# 10_ethernet100.net
KiCad netlist of a schematic drawn in Altium Designer
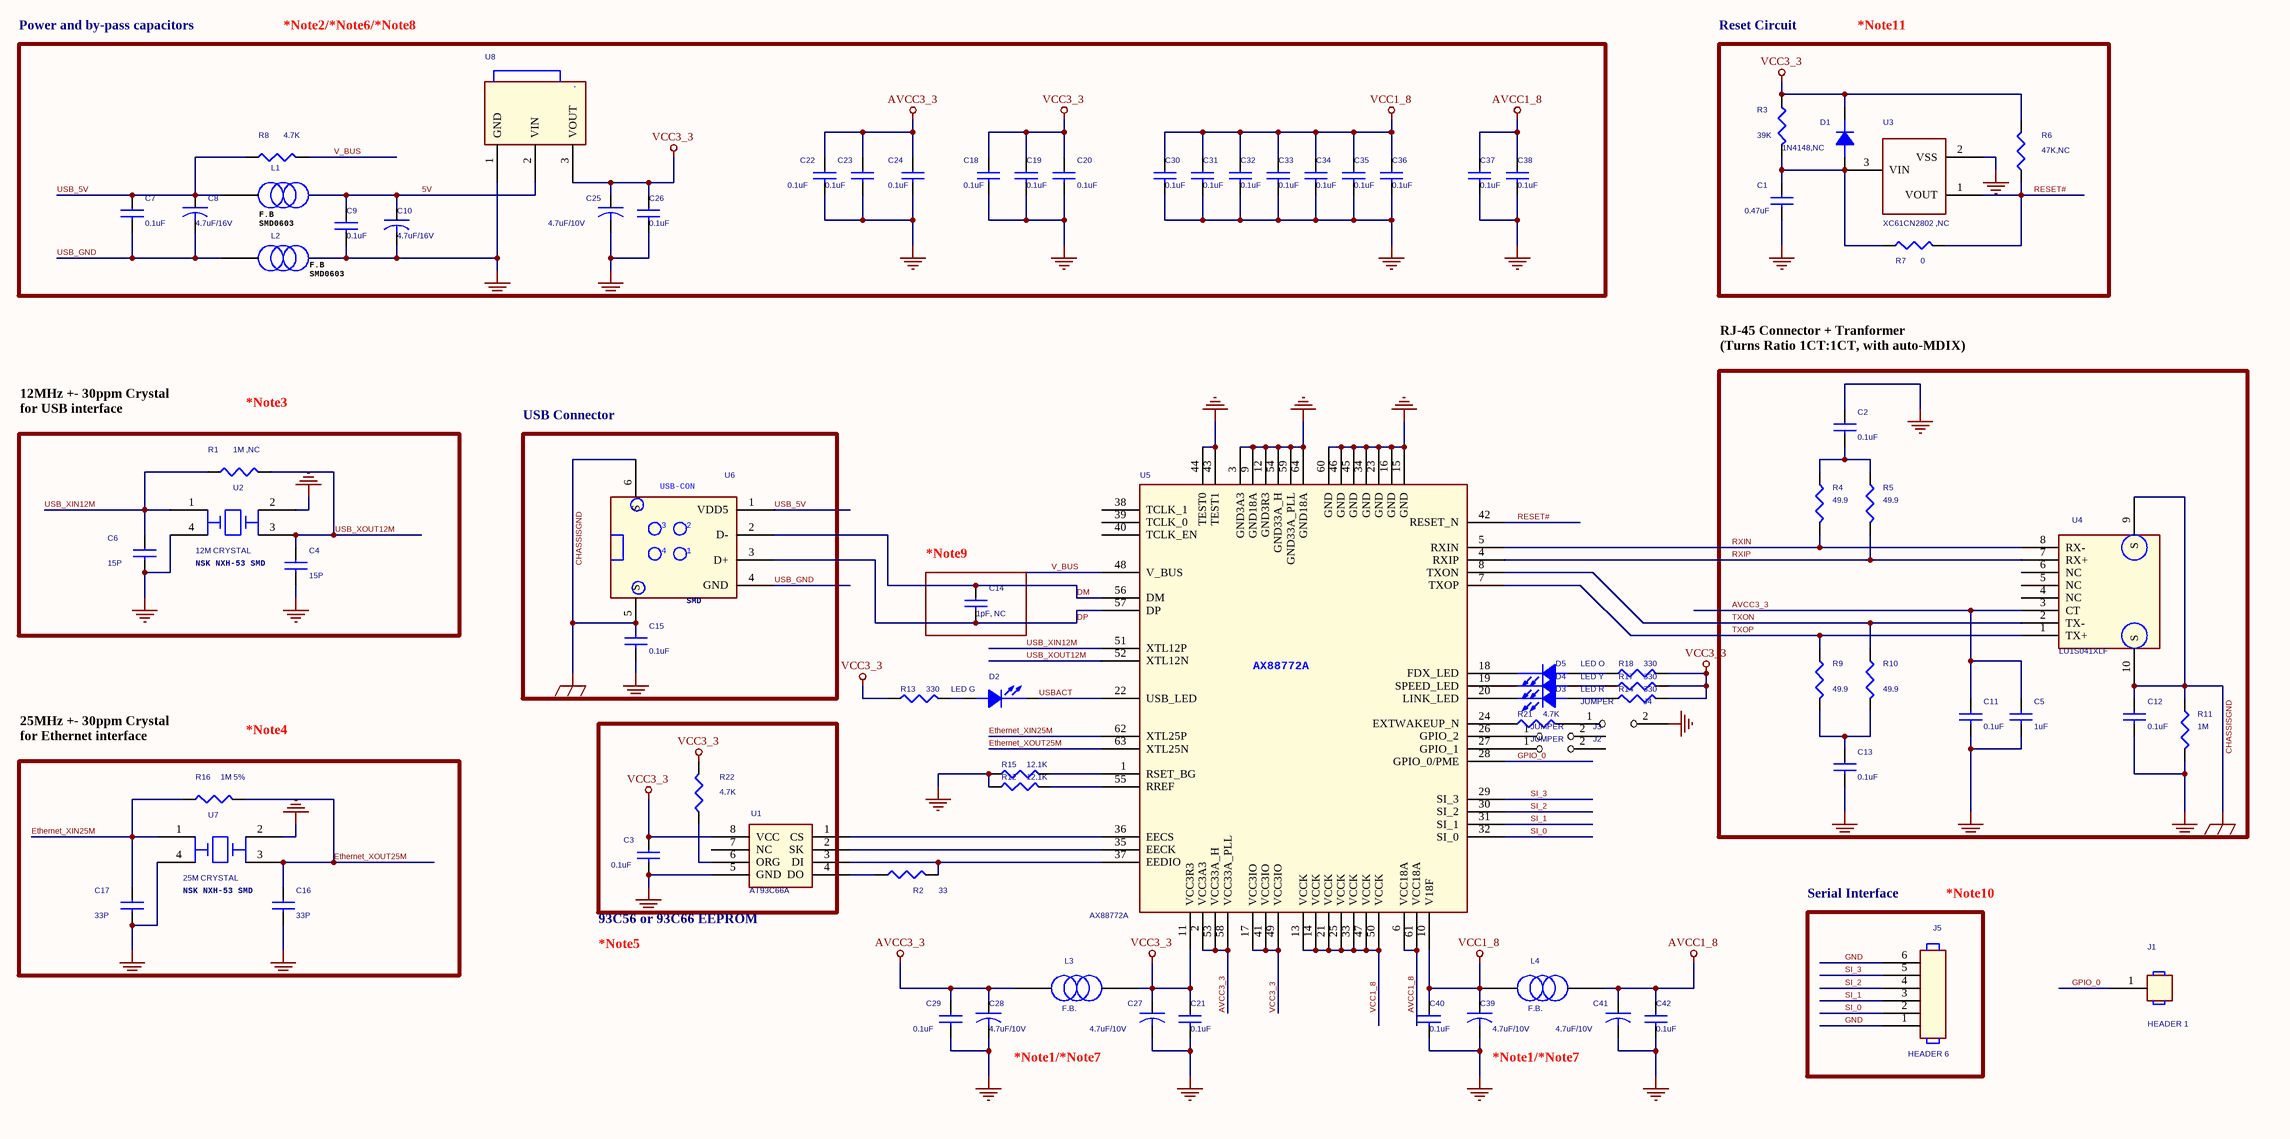
[diagram p0: 10_ethernet100.SchDoc]

(export (version "E")
  (design (tool "Eeschema 10.0.6"))
  (components
    (comp (ref "C1") (value "0.47uF") (libsource (lib "*") (part "CAP NP_Dup2")))
    (comp (ref "C2") (value "0.1uF") (libsource (lib "*") (part "CAP NP_Dup1")))
    (comp (ref "C3") (value "0.1uF") (libsource (lib "*") (part "CAP NP")))
    (comp (ref "C4") (value "15P") (libsource (lib "*") (part "CAP NP_Dup2")))
    (comp (ref "C5") (value "1uF") (libsource (lib "*") (part "CAP NP_Dup1")))
    (comp (ref "C6") (value "15P") (libsource (lib "*") (part "CAP NP_Dup2")))
    (comp (ref "C7") (value "0.1uF") (libsource (lib "*") (part "CAP NP_Dup2")))
    (comp (ref "C8") (value "4.7uF/16V") (libsource (lib "*") (part "CAP")))
    (comp (ref "C9") (value "0.1uF") (libsource (lib "*") (part "CAP NP_Dup2")))
    (comp (ref "C10") (value "4.7uF/16V") (libsource (lib "*") (part "CAP")))
    (comp (ref "C11") (value "0.1uF") (libsource (lib "*") (part "CAP NP_Dup1")))
    (comp (ref "C12") (value "0.1uF") (libsource (lib "*") (part "CAP NP_Dup1")))
    (comp (ref "C13") (value "0.1uF") (libsource (lib "*") (part "CAP NP_Dup1")))
    (comp (ref "C14") (value "1pF, NC") (libsource (lib "*") (part "CAP NP_Dup1")))
    (comp (ref "C15") (value "0.1uF") (libsource (lib "*") (part "CAP NP_Dup1")))
    (comp (ref "C16") (value "33P") (libsource (lib "*") (part "CAP NP_Dup2")))
    (comp (ref "C17") (value "33P") (libsource (lib "*") (part "CAP NP_Dup2")))
    (comp (ref "C18") (value "0.1uF") (libsource (lib "*") (part "CAP NP_Dup2")))
    (comp (ref "C19") (value "0.1uF") (libsource (lib "*") (part "CAP NP_Dup2")))
    (comp (ref "C20") (value "0.1uF") (libsource (lib "*") (part "CAP NP_Dup2")))
    (comp (ref "C21") (value "0.1uF") (libsource (lib "*") (part "CAP NP_Dup2")))
    (comp (ref "C22") (value "0.1uF") (libsource (lib "*") (part "CAP NP_Dup2")))
    (comp (ref "C23") (value "0.1uF") (libsource (lib "*") (part "CAP NP_Dup2")))
    (comp (ref "C24") (value "0.1uF") (libsource (lib "*") (part "CAP NP_Dup2")))
    (comp (ref "C25") (value "4.7uF/10V") (libsource (lib "*") (part "C")))
    (comp (ref "C26") (value "0.1uF") (libsource (lib "*") (part "CAP NP_Dup2")))
    (comp (ref "C27") (value "4.7uF/10V") (libsource (lib "*") (part "C")))
    (comp (ref "C28") (value "4.7uF/10V") (libsource (lib "*") (part "C")))
    (comp (ref "C29") (value "0.1uF") (libsource (lib "*") (part "CAP NP_Dup2")))
    (comp (ref "C30") (value "0.1uF") (libsource (lib "*") (part "CAP NP_Dup2")))
    (comp (ref "C31") (value "0.1uF") (libsource (lib "*") (part "CAP NP_Dup2")))
    (comp (ref "C32") (value "0.1uF") (libsource (lib "*") (part "CAP NP_Dup2")))
    (comp (ref "C33") (value "0.1uF") (libsource (lib "*") (part "CAP NP_Dup2")))
    (comp (ref "C34") (value "0.1uF") (libsource (lib "*") (part "CAP NP_Dup2")))
    (comp (ref "C35") (value "0.1uF") (libsource (lib "*") (part "CAP NP_Dup2")))
    (comp (ref "C36") (value "0.1uF") (libsource (lib "*") (part "CAP NP_Dup2")))
    (comp (ref "C37") (value "0.1uF") (libsource (lib "*") (part "CAP NP_Dup2")))
    (comp (ref "C38") (value "0.1uF") (libsource (lib "*") (part "CAP NP_Dup2")))
    (comp (ref "C39") (value "4.7uF/10V") (libsource (lib "*") (part "C")))
    (comp (ref "C40") (value "0.1uF") (libsource (lib "*") (part "CAP NP_Dup2")))
    (comp (ref "C41") (value "4.7uF/10V") (libsource (lib "*") (part "C")))
    (comp (ref "C42") (value "0.1uF") (libsource (lib "*") (part "CAP NP_Dup2")))
    (comp (ref "D1") (value "1N4148,NC") (libsource (lib "*") (part "DIODE")))
    (comp (ref "D2") (value "LED G") (libsource (lib "*") (part "LED")))
    (comp (ref "D3") (value "LED R") (libsource (lib "*") (part "LED")))
    (comp (ref "D4") (value "LED Y") (libsource (lib "*") (part "LED")))
    (comp (ref "D5") (value "LED O") (libsource (lib "*") (part "LED")))
    (comp (ref "J1") (value "HEADER 1") (libsource (lib "*") (part "HEADER 1")))
    (comp (ref "J2") (value "JUMPER") (libsource (lib "*") (part "JUMPER")))
    (comp (ref "J3") (value "JUMPER") (libsource (lib "*") (part "JUMPER")))
    (comp (ref "J4") (value "JUMPER") (libsource (lib "*") (part "JUMPER")))
    (comp (ref "J5") (value "HEADER 6") (libsource (lib "*") (part "HEADER 6")))
    (comp (ref "L1") (value "F.B.") (libsource (lib "*") (part "L")))
    (comp (ref "L2") (value "F.B.") (libsource (lib "*") (part "L")))
    (comp (ref "L3") (value "F.B.") (libsource (lib "*") (part "L")))
    (comp (ref "L4") (value "F.B.") (libsource (lib "*") (part "L")))
    (comp (ref "R1") (value "1M ,NC") (libsource (lib "*") (part "R_Dup1")))
    (comp (ref "R2") (value "33") (libsource (lib "*") (part "R")))
    (comp (ref "R3") (value "39K") (libsource (lib "*") (part "R_Dup1")))
    (comp (ref "R4") (value "49.9") (libsource (lib "*") (part "R_Dup1")))
    (comp (ref "R5") (value "49.9") (libsource (lib "*") (part "R_Dup1")))
    (comp (ref "R6") (value "47K,NC") (libsource (lib "*") (part "R")))
    (comp (ref "R7") (value "0") (libsource (lib "*") (part "R")))
    (comp (ref "R8") (value "4.7K") (libsource (lib "*") (part "R")))
    (comp (ref "R9") (value "49.9") (libsource (lib "*") (part "R_Dup1")))
    (comp (ref "R10") (value "49.9") (libsource (lib "*") (part "R_Dup1")))
    (comp (ref "R11") (value "1M") (libsource (lib "*") (part "R_Dup1")))
    (comp (ref "R12") (value "12.1K") (libsource (lib "*") (part "R_Dup1")))
    (comp (ref "R13") (value "330") (libsource (lib "*") (part "R")))
    (comp (ref "R14") (value "330") (libsource (lib "*") (part "R")))
    (comp (ref "R15") (value "12.1K") (libsource (lib "*") (part "R_Dup1")))
    (comp (ref "R16") (value "1M 5%") (libsource (lib "*") (part "R_Dup1")))
    (comp (ref "R17") (value "330") (libsource (lib "*") (part "R")))
    (comp (ref "R18") (value "330") (libsource (lib "*") (part "R")))
    (comp (ref "R21") (value "4.7K") (libsource (lib "*") (part "R_Dup1")))
    (comp (ref "R22") (value "4.7K") (libsource (lib "*") (part "R_0")))
    (comp (ref "U1") (value "AT93C66A") (libsource (lib "*") (part "93C56_2")))
    (comp (ref "U2") (value "12M CRYSTAL") (libsource (lib "*") (part "CRYSTAL4/SM")))
    (comp (ref "U3") (value "XC61CN2802 ,NC") (libsource (lib "*") (part "XC61G2802")))
    (comp (ref "U4") (value "LU1S041XLF") (libsource (lib "*") (part "LU1S041_1")))
    (comp (ref "U5") (value "AX88772A") (libsource (lib "*") (part "AX88772A 60PIN SIMPLE_4")))
    (comp (ref "U6") (value "USB-CON") (footprint "QSP") (libsource (lib "*") (part "USB-CON_0")))
    (comp (ref "U7") (value "25M CRYSTAL") (libsource (lib "*") (part "CRYSTAL4/SM")))
    (comp (ref "U8") (value "RT9161A-3.3V") (libsource (lib "*") (part "RT9161A-3.3V")))
  )
  (nets
    (net (code "1") (name "/5V") (class "Default")
      (node (ref "C10") (pin "1") (pinfunction "1_1") (pintype "passive"))
      (node (ref "C9") (pin "1") (pinfunction "1_1") (pintype "passive"))
      (node (ref "L1") (pin "2") (pinfunction "2_2") (pintype "passive"))
      (node (ref "U8") (pin "2") (pinfunction "VIN_2") (pintype "passive"))
    )
    (net (code "2") (name "/DM") (class "Default")
      (node (ref "C14") (pin "1") (pinfunction "1_1") (pintype "passive"))
      (node (ref "U5") (pin "56") (pinfunction "DM_56") (pintype "passive"))
      (node (ref "U6") (pin "2") (pinfunction "D-_2") (pintype "passive"))
    )
    (net (code "3") (name "/DP") (class "Default")
      (node (ref "C14") (pin "2") (pinfunction "2_2") (pintype "passive"))
      (node (ref "U5") (pin "57") (pinfunction "DP_57") (pintype "passive"))
      (node (ref "U6") (pin "3") (pinfunction "D+_3") (pintype "passive"))
    )
    (net (code "4") (name "/Ethernet_XIN25M") (class "Default")
      (node (ref "C17") (pin "1") (pinfunction "1_1") (pintype "passive"))
      (node (ref "R16") (pin "1") (pinfunction "1_1") (pintype "passive"))
      (node (ref "U5") (pin "62") (pinfunction "XTL25P_62") (pintype "passive"))
      (node (ref "U7") (pin "1") (pinfunction "1_1") (pintype "passive"))
    )
    (net (code "5") (name "/Ethernet_XOUT25M") (class "Default")
      (node (ref "C16") (pin "1") (pinfunction "1_1") (pintype "passive"))
      (node (ref "R16") (pin "2") (pinfunction "2_2") (pintype "passive"))
      (node (ref "U5") (pin "63") (pinfunction "XTL25N_63") (pintype "passive"))
      (node (ref "U7") (pin "3") (pinfunction "3_3") (pintype "passive"))
    )
    (net (code "6") (name "/GPIO_0") (class "Default")
      (node (ref "J1") (pin "1") (pinfunction "1_1") (pintype "passive"))
      (node (ref "U5") (pin "28") (pinfunction "GPIO_0/PME_28") (pintype "passive"))
    )
    (net (code "7") (name "/RESET#") (class "Default")
      (node (ref "R6") (pin "1") (pinfunction "1_1") (pintype "passive"))
      (node (ref "R7") (pin "2") (pinfunction "2_2") (pintype "passive"))
      (node (ref "U3") (pin "1") (pinfunction "VOUT_1") (pintype "passive"))
      (node (ref "U5") (pin "42") (pinfunction "RESET_N_42") (pintype "passive"))
    )
    (net (code "8") (name "/RXIN") (class "Default")
      (node (ref "R4") (pin "2") (pinfunction "2_2") (pintype "passive"))
      (node (ref "U4") (pin "8") (pinfunction "RX-_8") (pintype "passive"))
      (node (ref "U5") (pin "5") (pinfunction "RXIN_5") (pintype "passive"))
    )
    (net (code "9") (name "/RXIP") (class "Default")
      (node (ref "R5") (pin "2") (pinfunction "2_2") (pintype "passive"))
      (node (ref "U4") (pin "7") (pinfunction "RX+_7") (pintype "passive"))
      (node (ref "U5") (pin "4") (pinfunction "RXIP_4") (pintype "passive"))
    )
    (net (code "10") (name "/SI_0") (class "Default")
      (node (ref "J5") (pin "2") (pinfunction "2_2") (pintype "passive"))
      (node (ref "U5") (pin "32") (pinfunction "SI_0_32") (pintype "passive"))
    )
    (net (code "11") (name "/SI_1") (class "Default")
      (node (ref "J5") (pin "3") (pinfunction "3_3") (pintype "passive"))
      (node (ref "U5") (pin "31") (pinfunction "SI_1_31") (pintype "passive"))
    )
    (net (code "12") (name "/SI_2") (class "Default")
      (node (ref "J5") (pin "4") (pinfunction "4_4") (pintype "passive"))
      (node (ref "U5") (pin "30") (pinfunction "SI_2_30") (pintype "passive"))
    )
    (net (code "13") (name "/SI_3") (class "Default")
      (node (ref "J5") (pin "5") (pinfunction "5_5") (pintype "passive"))
      (node (ref "U5") (pin "29") (pinfunction "SI_3_29") (pintype "passive"))
    )
    (net (code "14") (name "/TXON") (class "Default")
      (node (ref "R10") (pin "1") (pinfunction "1_1") (pintype "passive"))
      (node (ref "U4") (pin "2") (pinfunction "TX-_2") (pintype "passive"))
      (node (ref "U5") (pin "8") (pinfunction "TXON_8") (pintype "passive"))
    )
    (net (code "15") (name "/TXOP") (class "Default")
      (node (ref "R9") (pin "1") (pinfunction "1_1") (pintype "passive"))
      (node (ref "U4") (pin "1") (pinfunction "TX+_1") (pintype "passive"))
      (node (ref "U5") (pin "7") (pinfunction "TXOP_7") (pintype "passive"))
    )
    (net (code "16") (name "/USBACT") (class "Default")
      (node (ref "D2") (pin "2") (pinfunction "CATHODE_2") (pintype "passive"))
      (node (ref "U5") (pin "22") (pinfunction "USB_LED_22") (pintype "passive"))
    )
    (net (code "17") (name "/USB_5V") (class "Default")
      (node (ref "C7") (pin "1") (pinfunction "1_1") (pintype "passive"))
      (node (ref "C8") (pin "1") (pinfunction "1_1") (pintype "passive"))
      (node (ref "L1") (pin "1") (pinfunction "1_1") (pintype "passive"))
      (node (ref "R8") (pin "1") (pinfunction "1_1") (pintype "passive"))
      (node (ref "U6") (pin "1") (pinfunction "VDD5_1") (pintype "passive"))
    )
    (net (code "18") (name "/USB_GND") (class "Default")
      (node (ref "C7") (pin "2") (pinfunction "2_2") (pintype "passive"))
      (node (ref "C8") (pin "2") (pinfunction "2_2") (pintype "passive"))
      (node (ref "L2") (pin "1") (pinfunction "1_1") (pintype "passive"))
      (node (ref "U6") (pin "4") (pinfunction "GND_4") (pintype "passive"))
    )
    (net (code "19") (name "/USB_XIN12M") (class "Default")
      (node (ref "C6") (pin "1") (pinfunction "1_1") (pintype "passive"))
      (node (ref "R1") (pin "1") (pinfunction "1_1") (pintype "passive"))
      (node (ref "U2") (pin "1") (pinfunction "1_1") (pintype "passive"))
      (node (ref "U5") (pin "51") (pinfunction "XTL12P_51") (pintype "passive"))
    )
    (net (code "20") (name "/USB_XOUT12M") (class "Default")
      (node (ref "C4") (pin "1") (pinfunction "1_1") (pintype "passive"))
      (node (ref "R1") (pin "2") (pinfunction "2_2") (pintype "passive"))
      (node (ref "U2") (pin "3") (pinfunction "3_3") (pintype "passive"))
      (node (ref "U5") (pin "52") (pinfunction "XTL12N_52") (pintype "passive"))
    )
    (net (code "21") (name "/V_BUS") (class "Default")
      (node (ref "R8") (pin "2") (pinfunction "2_2") (pintype "passive"))
      (node (ref "U5") (pin "48") (pinfunction "V_BUS_48") (pintype "passive"))
    )
    (net (code "22") (name "AVCC1_8") (class "Default")
      (node (ref "C37") (pin "1") (pinfunction "1_1") (pintype "passive"))
      (node (ref "C38") (pin "1") (pinfunction "1_1") (pintype "passive"))
      (node (ref "C41") (pin "1") (pinfunction "1_1") (pintype "passive"))
      (node (ref "C42") (pin "1") (pinfunction "1_1") (pintype "passive"))
      (node (ref "L4") (pin "2") (pinfunction "2_2") (pintype "passive"))
      (node (ref "U5") (pin "6") (pinfunction "VCC18A_6") (pintype "passive"))
      (node (ref "U5") (pin "61") (pinfunction "VCC18A_61") (pintype "passive"))
    )
    (net (code "23") (name "AVCC3_3") (class "Default")
      (node (ref "C11") (pin "1") (pinfunction "1_1") (pintype "passive"))
      (node (ref "C22") (pin "1") (pinfunction "1_1") (pintype "passive"))
      (node (ref "C23") (pin "1") (pinfunction "1_1") (pintype "passive"))
      (node (ref "C24") (pin "1") (pinfunction "1_1") (pintype "passive"))
      (node (ref "C28") (pin "1") (pinfunction "1_1") (pintype "passive"))
      (node (ref "C29") (pin "1") (pinfunction "1_1") (pintype "passive"))
      (node (ref "C5") (pin "1") (pinfunction "1_1") (pintype "passive"))
      (node (ref "L3") (pin "1") (pinfunction "1_1") (pintype "passive"))
      (node (ref "U4") (pin "3") (pinfunction "CT_3") (pintype "passive"))
      (node (ref "U5") (pin "2") (pinfunction "VCC3A3_2") (pintype "passive"))
      (node (ref "U5") (pin "53") (pinfunction "VCC33A_H_53") (pintype "passive"))
      (node (ref "U5") (pin "58") (pinfunction "VCC33A_PLL_58") (pintype "passive"))
    )
    (net (code "24") (name "CHASSISGND") (class "Default")
      (node (ref "C12") (pin "1") (pinfunction "1_1") (pintype "passive"))
      (node (ref "C15") (pin "1") (pinfunction "1_1") (pintype "passive"))
      (node (ref "R11") (pin "1") (pinfunction "1_1") (pintype "passive"))
      (node (ref "U4") (pin "10") (pinfunction "S_10") (pintype "passive"))
      (node (ref "U4") (pin "9") (pinfunction "S_9") (pintype "passive"))
      (node (ref "U6") (pin "5") (pinfunction "S_5") (pintype "passive"))
      (node (ref "U6") (pin "6") (pinfunction "S_6") (pintype "passive"))
    )
    (net (code "25") (name "GND") (class "Default")
      (node (ref "C1") (pin "2") (pinfunction "2_2") (pintype "passive"))
      (node (ref "C10") (pin "2") (pinfunction "2_2") (pintype "passive"))
      (node (ref "C11") (pin "2") (pinfunction "2_2") (pintype "passive"))
      (node (ref "C12") (pin "2") (pinfunction "2_2") (pintype "passive"))
      (node (ref "C13") (pin "2") (pinfunction "2_2") (pintype "passive"))
      (node (ref "C15") (pin "2") (pinfunction "2_2") (pintype "passive"))
      (node (ref "C16") (pin "2") (pinfunction "2_2") (pintype "passive"))
      (node (ref "C17") (pin "2") (pinfunction "2_2") (pintype "passive"))
      (node (ref "C18") (pin "2") (pinfunction "2_2") (pintype "passive"))
      (node (ref "C19") (pin "2") (pinfunction "2_2") (pintype "passive"))
      (node (ref "C2") (pin "1") (pinfunction "1_1") (pintype "passive"))
      (node (ref "C20") (pin "2") (pinfunction "2_2") (pintype "passive"))
      (node (ref "C21") (pin "2") (pinfunction "2_2") (pintype "passive"))
      (node (ref "C22") (pin "2") (pinfunction "2_2") (pintype "passive"))
      (node (ref "C23") (pin "2") (pinfunction "2_2") (pintype "passive"))
      (node (ref "C24") (pin "2") (pinfunction "2_2") (pintype "passive"))
      (node (ref "C25") (pin "2") (pinfunction "2_2") (pintype "passive"))
      (node (ref "C26") (pin "2") (pinfunction "2_2") (pintype "passive"))
      (node (ref "C27") (pin "2") (pinfunction "2_2") (pintype "passive"))
      (node (ref "C28") (pin "2") (pinfunction "2_2") (pintype "passive"))
      (node (ref "C29") (pin "2") (pinfunction "2_2") (pintype "passive"))
      (node (ref "C3") (pin "2") (pinfunction "2_2") (pintype "passive"))
      (node (ref "C30") (pin "2") (pinfunction "2_2") (pintype "passive"))
      (node (ref "C31") (pin "2") (pinfunction "2_2") (pintype "passive"))
      (node (ref "C32") (pin "2") (pinfunction "2_2") (pintype "passive"))
      (node (ref "C33") (pin "2") (pinfunction "2_2") (pintype "passive"))
      (node (ref "C34") (pin "2") (pinfunction "2_2") (pintype "passive"))
      (node (ref "C35") (pin "2") (pinfunction "2_2") (pintype "passive"))
      (node (ref "C36") (pin "2") (pinfunction "2_2") (pintype "passive"))
      (node (ref "C37") (pin "2") (pinfunction "2_2") (pintype "passive"))
      (node (ref "C38") (pin "2") (pinfunction "2_2") (pintype "passive"))
      (node (ref "C39") (pin "2") (pinfunction "2_2") (pintype "passive"))
      (node (ref "C4") (pin "2") (pinfunction "2_2") (pintype "passive"))
      (node (ref "C40") (pin "2") (pinfunction "2_2") (pintype "passive"))
      (node (ref "C41") (pin "2") (pinfunction "2_2") (pintype "passive"))
      (node (ref "C42") (pin "2") (pinfunction "2_2") (pintype "passive"))
      (node (ref "C5") (pin "2") (pinfunction "2_2") (pintype "passive"))
      (node (ref "C6") (pin "2") (pinfunction "2_2") (pintype "passive"))
      (node (ref "C9") (pin "2") (pinfunction "2_2") (pintype "passive"))
      (node (ref "J4") (pin "2") (pinfunction "2_2") (pintype "passive"))
      (node (ref "J5") (pin "1") (pinfunction "1_1") (pintype "passive"))
      (node (ref "J5") (pin "6") (pinfunction "6_6") (pintype "passive"))
      (node (ref "L2") (pin "2") (pinfunction "2_2") (pintype "passive"))
      (node (ref "R11") (pin "2") (pinfunction "2_2") (pintype "passive"))
      (node (ref "R12") (pin "1") (pinfunction "1_1") (pintype "passive"))
      (node (ref "R15") (pin "1") (pinfunction "1_1") (pintype "passive"))
      (node (ref "U1") (pin "5") (pinfunction "GND_5") (pintype "passive"))
      (node (ref "U2") (pin "2") (pinfunction "2_2") (pintype "passive"))
      (node (ref "U2") (pin "4") (pinfunction "4_4") (pintype "passive"))
      (node (ref "U3") (pin "2") (pinfunction "VSS_2") (pintype "passive"))
      (node (ref "U5") (pin "12") (pinfunction "GND3R3_12") (pintype "passive"))
      (node (ref "U5") (pin "15") (pinfunction "GND_15") (pintype "passive"))
      (node (ref "U5") (pin "16") (pinfunction "GND_16") (pintype "passive"))
      (node (ref "U5") (pin "23") (pinfunction "GND_23") (pintype "passive"))
      (node (ref "U5") (pin "3") (pinfunction "GND3A3_3") (pintype "passive"))
      (node (ref "U5") (pin "34") (pinfunction "GND_34") (pintype "passive"))
      (node (ref "U5") (pin "43") (pinfunction "TEST1_43") (pintype "passive"))
      (node (ref "U5") (pin "44") (pinfunction "TEST0_44") (pintype "passive"))
      (node (ref "U5") (pin "45") (pinfunction "GND_45") (pintype "passive"))
      (node (ref "U5") (pin "46") (pinfunction "GND_46") (pintype "passive"))
      (node (ref "U5") (pin "54") (pinfunction "GND33A_H_54") (pintype "passive"))
      (node (ref "U5") (pin "59") (pinfunction "GND33A_PLL_59") (pintype "passive"))
      (node (ref "U5") (pin "60") (pinfunction "GND_60") (pintype "passive"))
      (node (ref "U5") (pin "64") (pinfunction "GND18A_64") (pintype "passive"))
      (node (ref "U5") (pin "9") (pinfunction "GND18A_9") (pintype "passive"))
      (node (ref "U7") (pin "2") (pinfunction "2_2") (pintype "passive"))
      (node (ref "U7") (pin "4") (pinfunction "4_4") (pintype "passive"))
      (node (ref "U8") (pin "1") (pinfunction "GND_1") (pintype "passive"))
    )
    (net (code "26") (name "Net-(C2-Pad2)") (class "Default")
      (node (ref "C2") (pin "2") (pinfunction "2_2") (pintype "passive"))
      (node (ref "R4") (pin "1") (pinfunction "1_1") (pintype "passive"))
      (node (ref "R5") (pin "1") (pinfunction "1_1") (pintype "passive"))
    )
    (net (code "27") (name "Net-(C13-Pad1)") (class "Default")
      (node (ref "C13") (pin "1") (pinfunction "1_1") (pintype "passive"))
      (node (ref "R10") (pin "2") (pinfunction "2_2") (pintype "passive"))
      (node (ref "R9") (pin "2") (pinfunction "2_2") (pintype "passive"))
    )
    (net (code "28") (name "Net-(D1-A)") (class "Default")
      (node (ref "C1") (pin "1") (pinfunction "1_1") (pintype "passive"))
      (node (ref "D1") (pin "1") (pinfunction "A_1") (pintype "passive"))
      (node (ref "R3") (pin "2") (pinfunction "2_2") (pintype "passive"))
      (node (ref "R7") (pin "1") (pinfunction "1_1") (pintype "passive"))
      (node (ref "U3") (pin "3") (pinfunction "VIN_3") (pintype "passive"))
    )
    (net (code "29") (name "Net-(D2-ANODE)") (class "Default")
      (node (ref "D2") (pin "1") (pinfunction "ANODE_1") (pintype "passive"))
      (node (ref "R13") (pin "2") (pinfunction "2_2") (pintype "passive"))
    )
    (net (code "30") (name "Net-(D3-ANODE)") (class "Default")
      (node (ref "D3") (pin "1") (pinfunction "ANODE_1") (pintype "passive"))
      (node (ref "R14") (pin "1") (pinfunction "1_1") (pintype "passive"))
    )
    (net (code "31") (name "Net-(D3-CATHODE)") (class "Default")
      (node (ref "D3") (pin "2") (pinfunction "CATHODE_2") (pintype "passive"))
      (node (ref "U5") (pin "20") (pinfunction "LINK_LED_20") (pintype "passive"))
    )
    (net (code "32") (name "Net-(D4-ANODE)") (class "Default")
      (node (ref "D4") (pin "1") (pinfunction "ANODE_1") (pintype "passive"))
      (node (ref "R17") (pin "1") (pinfunction "1_1") (pintype "passive"))
    )
    (net (code "33") (name "Net-(D4-CATHODE)") (class "Default")
      (node (ref "D4") (pin "2") (pinfunction "CATHODE_2") (pintype "passive"))
      (node (ref "U5") (pin "19") (pinfunction "SPEED_LED_19") (pintype "passive"))
    )
    (net (code "34") (name "Net-(D5-ANODE)") (class "Default")
      (node (ref "D5") (pin "1") (pinfunction "ANODE_1") (pintype "passive"))
      (node (ref "R18") (pin "1") (pinfunction "1_1") (pintype "passive"))
    )
    (net (code "35") (name "Net-(D5-CATHODE)") (class "Default")
      (node (ref "D5") (pin "2") (pinfunction "CATHODE_2") (pintype "passive"))
      (node (ref "U5") (pin "18") (pinfunction "FDX_LED_18") (pintype "passive"))
    )
    (net (code "36") (name "Net-(J4-Pad1)") (class "Default")
      (node (ref "J4") (pin "1") (pinfunction "1_1") (pintype "passive"))
      (node (ref "R21") (pin "2") (pinfunction "2_2") (pintype "passive"))
    )
    (net (code "37") (name "Net-(U1-CS)") (class "Default")
      (node (ref "U1") (pin "1") (pinfunction "CS_1") (pintype "passive"))
      (node (ref "U5") (pin "36") (pinfunction "EECS_36") (pintype "passive"))
    )
    (net (code "38") (name "Net-(U1-DI)") (class "Default")
      (node (ref "R2") (pin "2") (pinfunction "2_2") (pintype "passive"))
      (node (ref "U1") (pin "3") (pinfunction "DI_3") (pintype "passive"))
      (node (ref "U5") (pin "37") (pinfunction "EEDIO_37") (pintype "passive"))
    )
    (net (code "39") (name "Net-(U1-DO)") (class "Default")
      (node (ref "R2") (pin "1") (pinfunction "1_1") (pintype "passive"))
      (node (ref "U1") (pin "4") (pinfunction "DO_4") (pintype "passive"))
    )
    (net (code "40") (name "Net-(U1-ORG)") (class "Default")
      (node (ref "R22") (pin "1") (pinfunction "1_1") (pintype "passive"))
      (node (ref "U1") (pin "6") (pinfunction "ORG_6") (pintype "passive"))
    )
    (net (code "41") (name "Net-(U1-SK)") (class "Default")
      (node (ref "U1") (pin "2") (pinfunction "SK_2") (pintype "passive"))
      (node (ref "U5") (pin "35") (pinfunction "EECK_35") (pintype "passive"))
    )
    (net (code "42") (name "Net-(U5-EXTWAKEUP_N)") (class "Default")
      (node (ref "R21") (pin "1") (pinfunction "1_1") (pintype "passive"))
      (node (ref "U5") (pin "24") (pinfunction "EXTWAKEUP_N_24") (pintype "passive"))
    )
    (net (code "43") (name "Net-(U5-GPIO_1)") (class "Default")
      (node (ref "J2") (pin "1") (pinfunction "1_1") (pintype "passive"))
      (node (ref "U5") (pin "27") (pinfunction "GPIO_1_27") (pintype "passive"))
    )
    (net (code "44") (name "Net-(U5-GPIO_2)") (class "Default")
      (node (ref "J3") (pin "1") (pinfunction "1_1") (pintype "passive"))
      (node (ref "U5") (pin "26") (pinfunction "GPIO_2_26") (pintype "passive"))
    )
    (net (code "45") (name "Net-(U5-RREF)") (class "Default")
      (node (ref "R12") (pin "2") (pinfunction "2_2") (pintype "passive"))
      (node (ref "U5") (pin "55") (pinfunction "RREF_55") (pintype "passive"))
    )
    (net (code "46") (name "Net-(U5-RSET_BG)") (class "Default")
      (node (ref "R15") (pin "2") (pinfunction "2_2") (pintype "passive"))
      (node (ref "U5") (pin "1") (pinfunction "RSET_BG_1") (pintype "passive"))
    )
    (net (code "47") (name "VCC1_8") (class "Default")
      (node (ref "C30") (pin "1") (pinfunction "1_1") (pintype "passive"))
      (node (ref "C31") (pin "1") (pinfunction "1_1") (pintype "passive"))
      (node (ref "C32") (pin "1") (pinfunction "1_1") (pintype "passive"))
      (node (ref "C33") (pin "1") (pinfunction "1_1") (pintype "passive"))
      (node (ref "C34") (pin "1") (pinfunction "1_1") (pintype "passive"))
      (node (ref "C35") (pin "1") (pinfunction "1_1") (pintype "passive"))
      (node (ref "C36") (pin "1") (pinfunction "1_1") (pintype "passive"))
      (node (ref "C39") (pin "1") (pinfunction "1_1") (pintype "passive"))
      (node (ref "C40") (pin "1") (pinfunction "1_1") (pintype "passive"))
      (node (ref "L4") (pin "1") (pinfunction "1_1") (pintype "passive"))
      (node (ref "U5") (pin "10") (pinfunction "V18F_10") (pintype "passive"))
      (node (ref "U5") (pin "13") (pinfunction "VCCK_13") (pintype "passive"))
      (node (ref "U5") (pin "14") (pinfunction "VCCK_14") (pintype "passive"))
      (node (ref "U5") (pin "21") (pinfunction "VCCK_21") (pintype "passive"))
      (node (ref "U5") (pin "25") (pinfunction "VCCK_25") (pintype "passive"))
      (node (ref "U5") (pin "33") (pinfunction "VCCK_33") (pintype "passive"))
      (node (ref "U5") (pin "47") (pinfunction "VCCK_47") (pintype "passive"))
      (node (ref "U5") (pin "50") (pinfunction "VCCK_50") (pintype "passive"))
    )
    (net (code "48") (name "VCC3_3") (class "Default")
      (node (ref "C18") (pin "1") (pinfunction "1_1") (pintype "passive"))
      (node (ref "C19") (pin "1") (pinfunction "1_1") (pintype "passive"))
      (node (ref "C20") (pin "1") (pinfunction "1_1") (pintype "passive"))
      (node (ref "C21") (pin "1") (pinfunction "1_1") (pintype "passive"))
      (node (ref "C25") (pin "1") (pinfunction "1_1") (pintype "passive"))
      (node (ref "C26") (pin "1") (pinfunction "1_1") (pintype "passive"))
      (node (ref "C27") (pin "1") (pinfunction "1_1") (pintype "passive"))
      (node (ref "C3") (pin "1") (pinfunction "1_1") (pintype "passive"))
      (node (ref "D1") (pin "2") (pinfunction "K_2") (pintype "passive"))
      (node (ref "L3") (pin "2") (pinfunction "2_2") (pintype "passive"))
      (node (ref "R13") (pin "1") (pinfunction "1_1") (pintype "passive"))
      (node (ref "R14") (pin "2") (pinfunction "2_2") (pintype "passive"))
      (node (ref "R17") (pin "2") (pinfunction "2_2") (pintype "passive"))
      (node (ref "R18") (pin "2") (pinfunction "2_2") (pintype "passive"))
      (node (ref "R22") (pin "2") (pinfunction "2_2") (pintype "passive"))
      (node (ref "R3") (pin "1") (pinfunction "1_1") (pintype "passive"))
      (node (ref "R6") (pin "2") (pinfunction "2_2") (pintype "passive"))
      (node (ref "U1") (pin "8") (pinfunction "VCC_8") (pintype "passive"))
      (node (ref "U5") (pin "11") (pinfunction "VCC3R3_11") (pintype "passive"))
      (node (ref "U5") (pin "17") (pinfunction "VCC3IO_17") (pintype "passive"))
      (node (ref "U5") (pin "41") (pinfunction "VCC3IO_41") (pintype "passive"))
      (node (ref "U5") (pin "49") (pinfunction "VCC3IO_49") (pintype "passive"))
      (node (ref "U8") (pin "3") (pinfunction "VOUT_3") (pintype "passive"))
    )
    (net (code "49") (name "unconnected-(J2-Pad2)") (class "Default")
      (node (ref "J2") (pin "2") (pinfunction "2_2") (pintype "passive"))
    )
    (net (code "50") (name "unconnected-(J3-Pad2)") (class "Default")
      (node (ref "J3") (pin "2") (pinfunction "2_2") (pintype "passive"))
    )
    (net (code "51") (name "unconnected-(U1-NC-Pad7)") (class "Default")
      (node (ref "U1") (pin "7") (pinfunction "NC_7") (pintype "passive"))
    )
    (net (code "52") (name "unconnected-(U4-NC-Pad4)") (class "Default")
      (node (ref "U4") (pin "4") (pinfunction "NC_4") (pintype "passive"))
    )
    (net (code "53") (name "unconnected-(U4-NC-Pad5)") (class "Default")
      (node (ref "U4") (pin "5") (pinfunction "NC_5") (pintype "passive"))
    )
    (net (code "54") (name "unconnected-(U4-NC-Pad6)") (class "Default")
      (node (ref "U4") (pin "6") (pinfunction "NC_6") (pintype "passive"))
    )
    (net (code "55") (name "unconnected-(U5-TCLK_0-Pad39)") (class "Default")
      (node (ref "U5") (pin "39") (pinfunction "TCLK_0_39") (pintype "passive"))
    )
    (net (code "56") (name "unconnected-(U5-TCLK_1-Pad38)") (class "Default")
      (node (ref "U5") (pin "38") (pinfunction "TCLK_1_38") (pintype "passive"))
    )
    (net (code "57") (name "unconnected-(U5-TCLK_EN-Pad40)") (class "Default")
      (node (ref "U5") (pin "40") (pinfunction "TCLK_EN_40") (pintype "passive"))
    )
  )
)
